# Sensors.net
KiCad netlist of a schematic drawn in Altium Designer
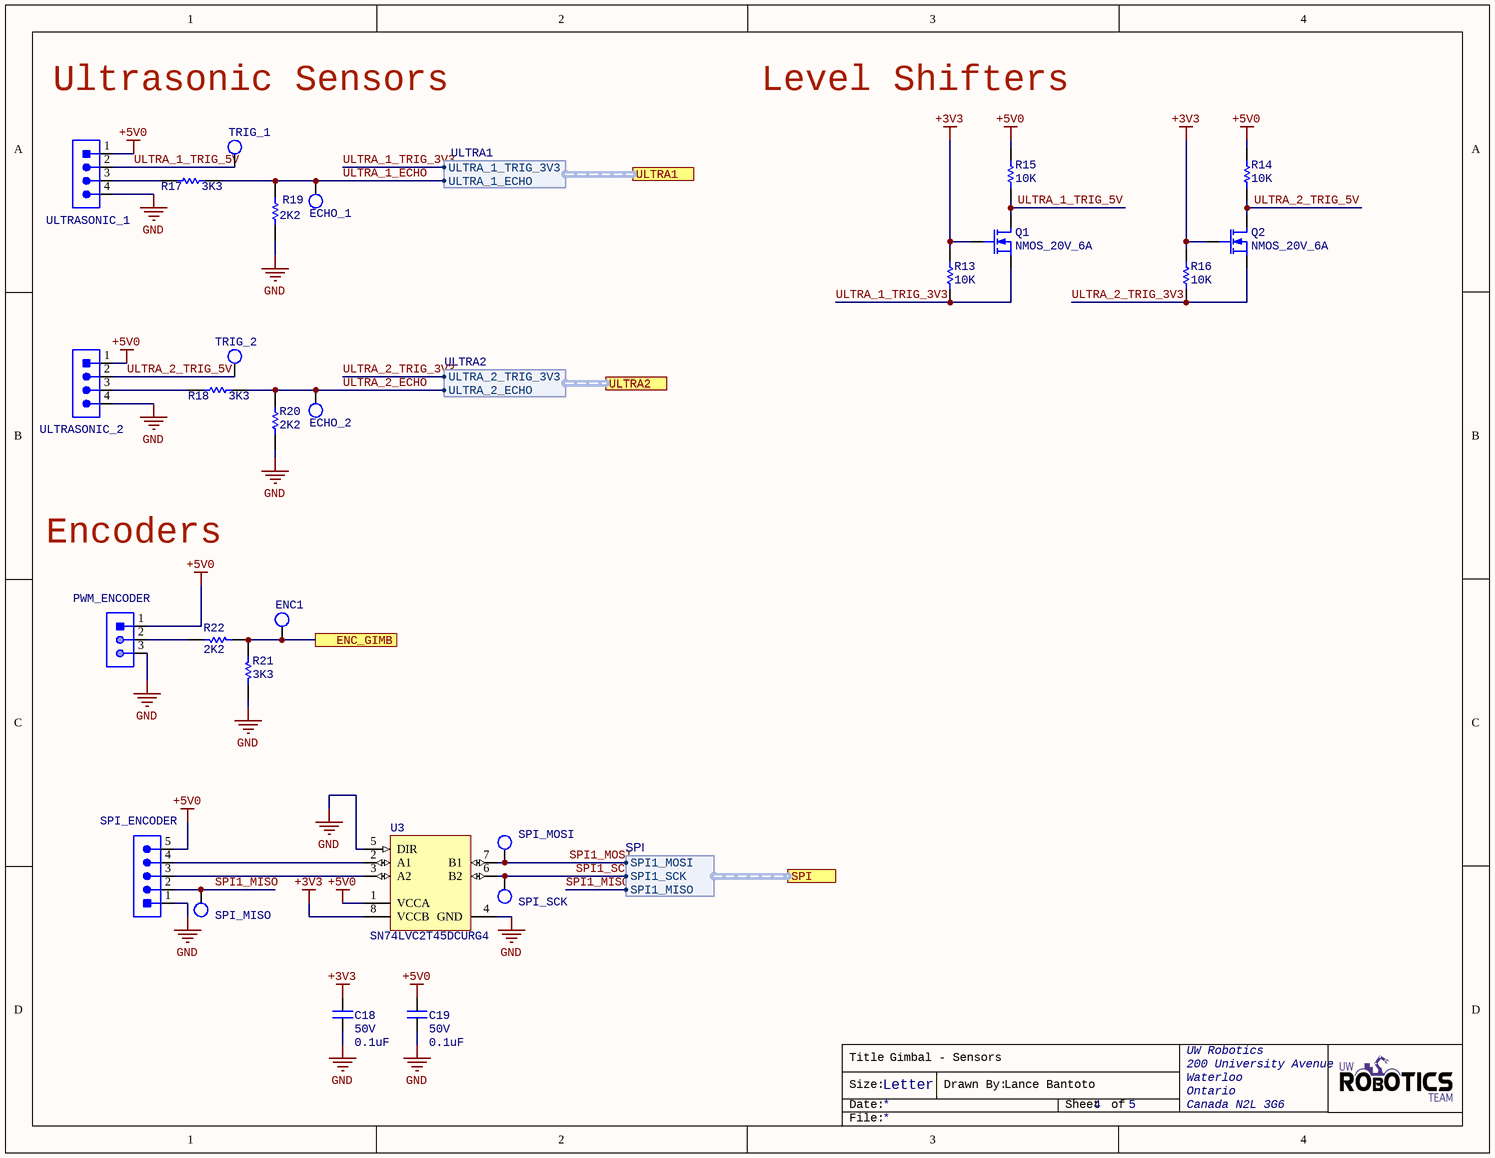
[diagram p0: Sensors.SchDoc]

(export (version "E")
  (design (tool "Eeschema 10.0.6"))
  (components
    (comp (ref "C18")
      (value "0.1uF")
      (footprint "CAPC0603(1608)55_N")
      (description "CAP CER 0.1UF 50V X7R 0603")
      (fields
        (field (name "MPN") "CC0603KRX7R9BB104")
        (field (name "MANUFACTURER") "Yageo")
        (field (name "VOLTAGE RATING") "50V")
      )
      (libsource (lib "UWRT_Schematic_Library_2020") (part "CAP_0.1uF_50V_0603"))
    )
    (comp (ref "C19")
      (value "0.1uF")
      (footprint "CAPC0603(1608)55_N")
      (description "CAP CER 0.1UF 50V X7R 0603")
      (fields
        (field (name "MPN") "CC0603KRX7R9BB104")
        (field (name "MANUFACTURER") "Yageo")
        (field (name "VOLTAGE RATING") "50V")
      )
      (libsource (lib "UWRT_Schematic_Library_2020") (part "CAP_0.1uF_50V_0603"))
    )
    (comp (ref "ECHO_1")
      (value "TESTPOINT_LOOP")
      (footprint "TESTPOINT_LOOP")
      (description "Loop testpoint through-hole pad")
      (fields (field (name "MANUFACTURER") "Keystone Electronics"))
      (libsource (lib "UWRT_Schematic_Library_2020") (part "TESTPOINT_LOOP"))
    )
    (comp (ref "ECHO_2")
      (value "TESTPOINT_LOOP")
      (footprint "TESTPOINT_LOOP")
      (description "Loop testpoint through-hole pad")
      (fields (field (name "MANUFACTURER") "Keystone Electronics"))
      (libsource (lib "UWRT_Schematic_Library_2020") (part "TESTPOINT_LOOP"))
    )
    (comp (ref "ENC1")
      (value "TESTPOINT_LOOP")
      (footprint "TESTPOINT_LOOP")
      (description "Loop testpoint through-hole pad")
      (fields (field (name "MANUFACTURER") "Keystone Electronics"))
      (libsource (lib "UWRT_Schematic_Library_2020") (part "TESTPOINT_LOOP"))
    )
    (comp (ref "PWM_ENCODER")
      (value "CON_3M_SM4")
      (footprint "JST-B3B-SM4-TB")
      (fields
        (field (name "MANUFACTURER") "JST")
        (field (name "MANUFACTURER PART NUMBER") "B3B-PH-SM4-TB(LF)(SN)")
      )
      (libsource (lib "UWRT_Schematic_Library_2020") (part "CON_3M_SM4"))
    )
    (comp (ref "Q1")
      (value "NMOS_20V_6A")
      (footprint "NMOS_SOT23-3")
      (description "MOSFET N-CH 20V 6A SOT23")
      (fields (field (name "MPN") "AO3420") (field (name "MANUFACTURER") "Alpha & Omega"))
      (libsource (lib "UWRT_Schematic_Library_2020") (part "NMOS_20V_6A"))
    )
    (comp (ref "Q2")
      (value "NMOS_20V_6A")
      (footprint "NMOS_SOT23-3")
      (description "MOSFET N-CH 20V 6A SOT23")
      (fields (field (name "MPN") "AO3420") (field (name "MANUFACTURER") "Alpha & Omega"))
      (libsource (lib "UWRT_Schematic_Library_2020") (part "NMOS_20V_6A"))
    )
    (comp (ref "R13")
      (value "10K")
      (footprint "RESC0603(1608)_N")
      (description "RES SMD 10K OHM 5% 1/10W 0603")
      (fields (field (name "MANUFACTURER") "Yageo") (field (name "MPN") "RC0603JR-0710KL"))
      (libsource (lib "UWRT_Schematic_Library_2020") (part "RES_10K_0603"))
    )
    (comp (ref "R14")
      (value "10K")
      (footprint "RESC0603(1608)_N")
      (description "RES SMD 10K OHM 5% 1/10W 0603")
      (fields (field (name "MANUFACTURER") "Yageo") (field (name "MPN") "RC0603JR-0710KL"))
      (libsource (lib "UWRT_Schematic_Library_2020") (part "RES_10K_0603"))
    )
    (comp (ref "R15")
      (value "10K")
      (footprint "RESC0603(1608)_N")
      (description "RES SMD 10K OHM 5% 1/10W 0603")
      (fields (field (name "MANUFACTURER") "Yageo") (field (name "MPN") "RC0603JR-0710KL"))
      (libsource (lib "UWRT_Schematic_Library_2020") (part "RES_10K_0603"))
    )
    (comp (ref "R16")
      (value "10K")
      (footprint "RESC0603(1608)_N")
      (description "RES SMD 10K OHM 5% 1/10W 0603")
      (fields (field (name "MANUFACTURER") "Yageo") (field (name "MPN") "RC0603JR-0710KL"))
      (libsource (lib "UWRT_Schematic_Library_2020") (part "RES_10K_0603"))
    )
    (comp (ref "R17")
      (value "3K3")
      (footprint "RESC0603(1608)_N")
      (description "RES SMD 3.3K OHM 5% 1/10W 0603")
      (fields (field (name "MANUFACTURER") "Yageo") (field (name "TOLERANCE") "5%"))
      (libsource (lib "UWRT_Schematic_Library_2020") (part "RES_3K3_0603"))
    )
    (comp (ref "R18")
      (value "3K3")
      (footprint "RESC0603(1608)_N")
      (description "RES SMD 3.3K OHM 5% 1/10W 0603")
      (fields (field (name "MANUFACTURER") "Yageo") (field (name "TOLERANCE") "5%"))
      (libsource (lib "UWRT_Schematic_Library_2020") (part "RES_3K3_0603"))
    )
    (comp (ref "R19")
      (value "2K2")
      (footprint "RESC0603(1608)_N")
      (description "RES SMD 2.2K OHM 1% 1/10W 0603")
      (fields (field (name "MANUFACTURER") "Yageo") (field (name "TOLERANCE") "1%"))
      (libsource (lib "UWRT_Schematic_Library_2020") (part "RES_2K2_0603"))
    )
    (comp (ref "R20")
      (value "2K2")
      (footprint "RESC0603(1608)_N")
      (description "RES SMD 2.2K OHM 1% 1/10W 0603")
      (fields (field (name "MANUFACTURER") "Yageo") (field (name "TOLERANCE") "1%"))
      (libsource (lib "UWRT_Schematic_Library_2020") (part "RES_2K2_0603"))
    )
    (comp (ref "R21")
      (value "3K3")
      (footprint "RESC0603(1608)_N")
      (description "RES SMD 3.3K OHM 5% 1/10W 0603")
      (fields (field (name "MANUFACTURER") "Yageo") (field (name "TOLERANCE") "5%"))
      (libsource (lib "UWRT_Schematic_Library_2020") (part "RES_3K3_0603"))
    )
    (comp (ref "R22")
      (value "2K2")
      (footprint "RESC0603(1608)_N")
      (description "RES SMD 2.2K OHM 1% 1/10W 0603")
      (fields (field (name "MANUFACTURER") "Yageo") (field (name "TOLERANCE") "1%"))
      (libsource (lib "UWRT_Schematic_Library_2020") (part "RES_2K2_0603"))
    )
    (comp (ref "SPI_ENCODER")
      (value "CON_5M_SM4")
      (footprint "JST-B5B-SM4-TB")
      (fields
        (field (name "MANUFACTURER") "JST")
        (field (name "MANUFACTURER PART NUMBER") "B5B-PH-SM4-TB(LF)(SN)")
      )
      (libsource (lib "UWRT_Schematic_Library_2020") (part "CON_5M_SM4"))
    )
    (comp (ref "SPI_MISO")
      (value "TESTPOINT_LOOP")
      (footprint "TESTPOINT_LOOP")
      (description "Loop testpoint through-hole pad")
      (fields (field (name "MANUFACTURER") "Keystone Electronics"))
      (libsource (lib "UWRT_Schematic_Library_2020") (part "TESTPOINT_LOOP"))
    )
    (comp (ref "SPI_MOSI")
      (value "TESTPOINT_LOOP")
      (footprint "TESTPOINT_LOOP")
      (description "Loop testpoint through-hole pad")
      (fields (field (name "MANUFACTURER") "Keystone Electronics"))
      (libsource (lib "UWRT_Schematic_Library_2020") (part "TESTPOINT_LOOP"))
    )
    (comp (ref "SPI_SCK")
      (value "TESTPOINT_LOOP")
      (footprint "TESTPOINT_LOOP")
      (description "Loop testpoint through-hole pad")
      (fields (field (name "MANUFACTURER") "Keystone Electronics"))
      (libsource (lib "UWRT_Schematic_Library_2020") (part "TESTPOINT_LOOP"))
    )
    (comp (ref "TRIG_1")
      (value "TESTPOINT_LOOP")
      (footprint "TESTPOINT_LOOP")
      (description "Loop testpoint through-hole pad")
      (fields (field (name "MANUFACTURER") "Keystone Electronics"))
      (libsource (lib "UWRT_Schematic_Library_2020") (part "TESTPOINT_LOOP"))
    )
    (comp (ref "TRIG_2")
      (value "TESTPOINT_LOOP")
      (footprint "TESTPOINT_LOOP")
      (description "Loop testpoint through-hole pad")
      (fields (field (name "MANUFACTURER") "Keystone Electronics"))
      (libsource (lib "UWRT_Schematic_Library_2020") (part "TESTPOINT_LOOP"))
    )
    (comp (ref "U3")
      (value "SN74LVC2T45DCURG4")
      (footprint "DCU0008A_L")
      (fields
        (field (name "MANUFACTURER") "Texas Instruments")
        (field (name "GENERIC PART NUMBER") "SN74LVC2T45")
      )
      (libsource (lib "Altium Content Vault") (part "TI-SN74XVC2T45-8"))
    )
    (comp (ref "ULTRASONIC_1")
      (value "CON_4M_SM4")
      (footprint "JST-B4B-SM4-TB")
      (fields
        (field (name "MANUFACTURER") "JST")
        (field (name "MANUFACTURER PART NUMBER") "B4B-PH-SM4-TB(LF)(SN)")
      )
      (libsource (lib "UWRT_Schematic_Library_2020") (part "CON_4M_SM4"))
    )
    (comp (ref "ULTRASONIC_2")
      (value "CON_4M_SM4")
      (footprint "JST-B4B-SM4-TB")
      (fields
        (field (name "MANUFACTURER") "JST")
        (field (name "MANUFACTURER PART NUMBER") "B4B-PH-SM4-TB(LF)(SN)")
      )
      (libsource (lib "UWRT_Schematic_Library_2020") (part "CON_4M_SM4"))
    )
  )
  (nets
    (net (code "4") (name "+3V3") (class "Default")
      (node (ref "C18") (pin "2") (pinfunction "2_2") (pintype "passive"))
      (node (ref "Q1") (pin "1") (pinfunction "G_1") (pintype "passive"))
      (node (ref "Q2") (pin "1") (pinfunction "G_1") (pintype "passive"))
      (node (ref "R13") (pin "1") (pinfunction "1_1") (pintype "passive"))
      (node (ref "R16") (pin "1") (pinfunction "1_1") (pintype "passive"))
      (node (ref "U3") (pin "8") (pinfunction "VCCB_8") (pintype "power_in"))
    )
    (net (code "5") (name "+5V0") (class "Default")
      (node (ref "C19") (pin "2") (pinfunction "2_2") (pintype "passive"))
      (node (ref "PWM_ENCODER") (pin "1") (pinfunction "1_1") (pintype "passive"))
      (node (ref "R14") (pin "2") (pinfunction "2_2") (pintype "passive"))
      (node (ref "R15") (pin "2") (pinfunction "2_2") (pintype "passive"))
      (node (ref "SPI_ENCODER") (pin "5") (pinfunction "5_5") (pintype "passive"))
      (node (ref "U3") (pin "1") (pinfunction "VCCA_1") (pintype "power_in"))
      (node (ref "ULTRASONIC_1") (pin "1") (pinfunction "1_1") (pintype "passive"))
      (node (ref "ULTRASONIC_2") (pin "1") (pinfunction "1_1") (pintype "passive"))
    )
    (net (code "6") (name "/ENC_GIMB") (class "Default")
      (node (ref "ENC1") (pin "1") (pintype "passive"))
      (node (ref "R21") (pin "1") (pinfunction "1_1") (pintype "passive"))
      (node (ref "R22") (pin "1") (pinfunction "1_1") (pintype "passive"))
    )
    (net (code "7") (name "/SPI1_MISO") (class "Default")
      (node (ref "SPI_ENCODER") (pin "2") (pinfunction "2_2") (pintype "passive"))
      (node (ref "SPI_MISO") (pin "1") (pintype "passive"))
    )
    (net (code "8") (name "/SPI1_MOSI") (class "Default")
      (node (ref "SPI_MOSI") (pin "1") (pintype "passive"))
      (node (ref "U3") (pin "7") (pinfunction "B1_7") (pintype "bidirectional"))
    )
    (net (code "9") (name "/SPI1_SCK") (class "Default")
      (node (ref "SPI_SCK") (pin "1") (pintype "passive"))
      (node (ref "U3") (pin "6") (pinfunction "B2_6") (pintype "bidirectional"))
    )
    (net (code "10") (name "/ULTRA_1_ECHO") (class "Default")
      (node (ref "ECHO_1") (pin "1") (pintype "passive"))
      (node (ref "R17") (pin "1") (pinfunction "1_1") (pintype "passive"))
      (node (ref "R19") (pin "2") (pinfunction "2_2") (pintype "passive"))
    )
    (net (code "11") (name "/ULTRA_1_TRIG_3V3") (class "Default")
      (node (ref "Q1") (pin "2") (pinfunction "S_2") (pintype "passive"))
      (node (ref "R13") (pin "2") (pinfunction "2_2") (pintype "passive"))
    )
    (net (code "12") (name "/ULTRA_1_TRIG_5V") (class "Default")
      (node (ref "Q1") (pin "3") (pinfunction "D_3") (pintype "passive"))
      (node (ref "R15") (pin "1") (pinfunction "1_1") (pintype "passive"))
      (node (ref "TRIG_1") (pin "1") (pintype "passive"))
      (node (ref "ULTRASONIC_1") (pin "2") (pinfunction "2_2") (pintype "passive"))
    )
    (net (code "13") (name "/ULTRA_2_ECHO") (class "Default")
      (node (ref "ECHO_2") (pin "1") (pintype "passive"))
      (node (ref "R18") (pin "1") (pinfunction "1_1") (pintype "passive"))
      (node (ref "R20") (pin "2") (pinfunction "2_2") (pintype "passive"))
    )
    (net (code "14") (name "/ULTRA_2_TRIG_3V3") (class "Default")
      (node (ref "Q2") (pin "2") (pinfunction "S_2") (pintype "passive"))
      (node (ref "R16") (pin "2") (pinfunction "2_2") (pintype "passive"))
    )
    (net (code "15") (name "/ULTRA_2_TRIG_5V") (class "Default")
      (node (ref "Q2") (pin "3") (pinfunction "D_3") (pintype "passive"))
      (node (ref "R14") (pin "1") (pinfunction "1_1") (pintype "passive"))
      (node (ref "TRIG_2") (pin "1") (pintype "passive"))
      (node (ref "ULTRASONIC_2") (pin "2") (pinfunction "2_2") (pintype "passive"))
    )
    (net (code "19") (name "GND") (class "Default")
      (node (ref "C18") (pin "1") (pinfunction "1_1") (pintype "passive"))
      (node (ref "C19") (pin "1") (pinfunction "1_1") (pintype "passive"))
      (node (ref "PWM_ENCODER") (pin "3") (pinfunction "3_3") (pintype "passive"))
      (node (ref "R19") (pin "1") (pinfunction "1_1") (pintype "passive"))
      (node (ref "R20") (pin "1") (pinfunction "1_1") (pintype "passive"))
      (node (ref "R21") (pin "2") (pinfunction "2_2") (pintype "passive"))
      (node (ref "SPI_ENCODER") (pin "1") (pinfunction "1_1") (pintype "passive"))
      (node (ref "U3") (pin "4") (pinfunction "GND_4") (pintype "power_in"))
      (node (ref "U3") (pin "5") (pinfunction "DIR_5") (pintype "input"))
      (node (ref "ULTRASONIC_1") (pin "4") (pinfunction "4_4") (pintype "passive"))
      (node (ref "ULTRASONIC_2") (pin "4") (pinfunction "4_4") (pintype "passive"))
    )
    (net (code "20") (name "Net-(PWM_ENCODER-Pad2)") (class "Default")
      (node (ref "PWM_ENCODER") (pin "2") (pinfunction "2_2") (pintype "passive"))
      (node (ref "R22") (pin "2") (pinfunction "2_2") (pintype "passive"))
    )
    (net (code "21") (name "Net-(R17-Pad2)") (class "Default")
      (node (ref "R17") (pin "2") (pinfunction "2_2") (pintype "passive"))
      (node (ref "ULTRASONIC_1") (pin "3") (pinfunction "3_3") (pintype "passive"))
    )
    (net (code "22") (name "Net-(R18-Pad2)") (class "Default")
      (node (ref "R18") (pin "2") (pinfunction "2_2") (pintype "passive"))
      (node (ref "ULTRASONIC_2") (pin "3") (pinfunction "3_3") (pintype "passive"))
    )
    (net (code "23") (name "Net-(U3-A1)") (class "Default")
      (node (ref "SPI_ENCODER") (pin "4") (pinfunction "4_4") (pintype "passive"))
      (node (ref "U3") (pin "2") (pinfunction "A1_2") (pintype "bidirectional"))
    )
    (net (code "24") (name "Net-(U3-A2)") (class "Default")
      (node (ref "SPI_ENCODER") (pin "3") (pinfunction "3_3") (pintype "passive"))
      (node (ref "U3") (pin "3") (pinfunction "A2_3") (pintype "bidirectional"))
    )
  )
)
